# SmartSocket.net
KiCad netlist of a schematic drawn in Altium Designer
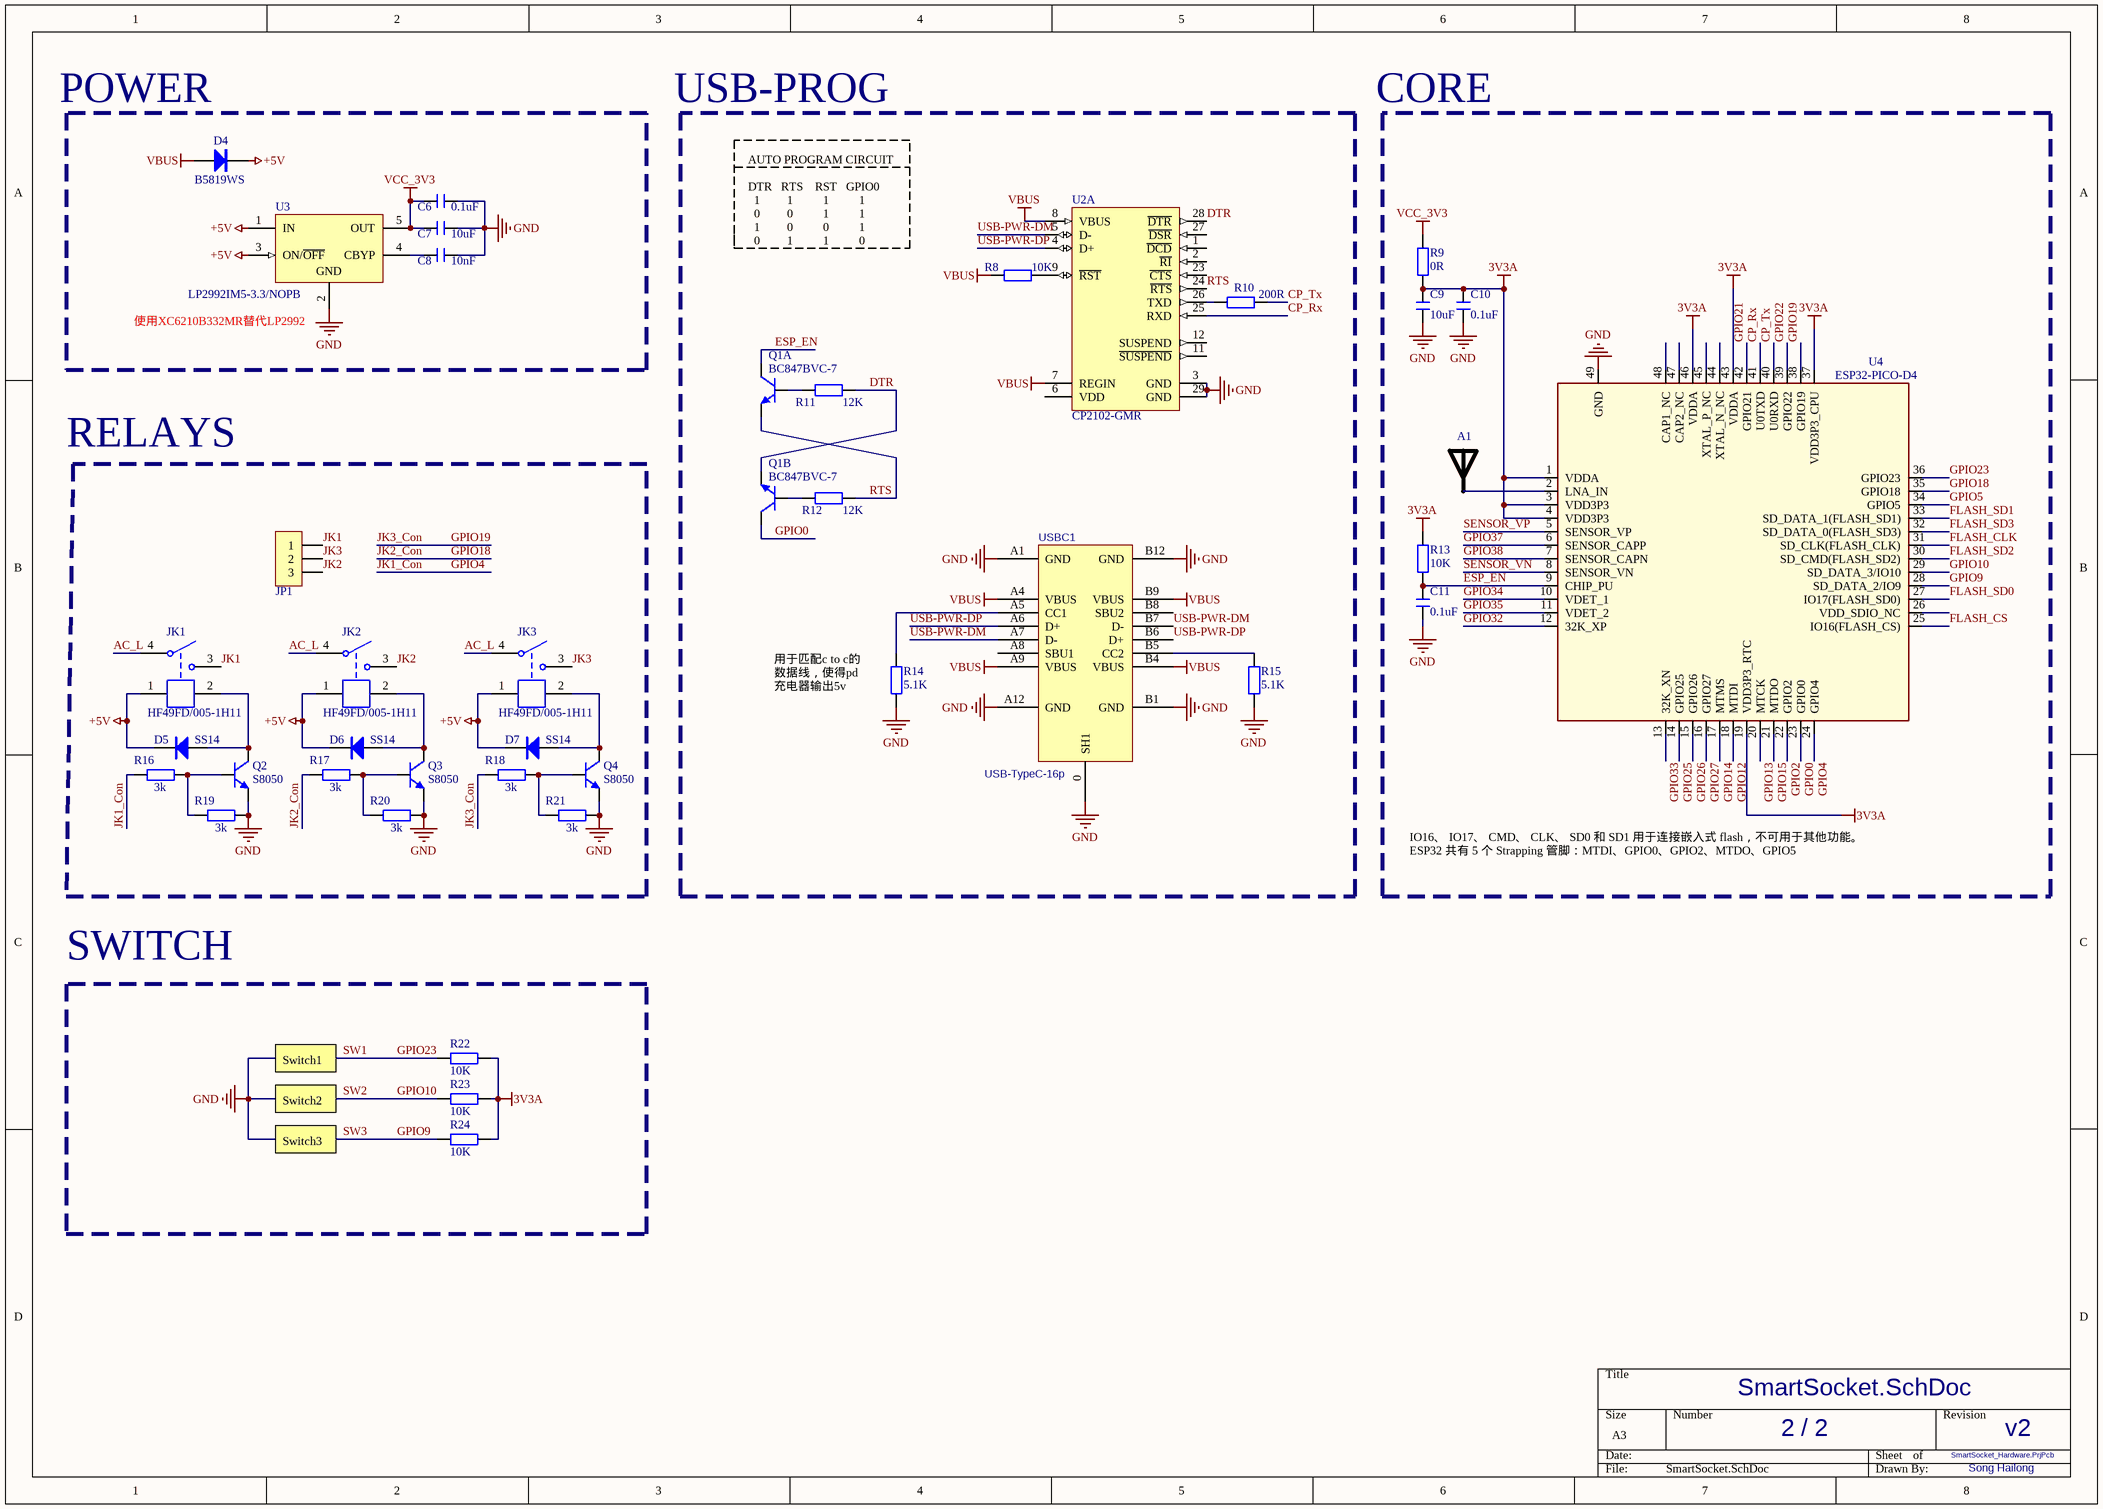
[diagram p0: SmartSocket.SchDoc]

(export (version "E")
  (design (tool "Eeschema 10.0.6"))
  (components
    (comp (ref "A1")
      (value "AN2051-245")
      (footprint "AN2051-245")
      (description "天线AN2051-245")
      (libsource (lib "海龍集成库") (part "ANT-Rainsun-AP2051"))
    )
    (comp (ref "C6")
      (value "0.1uF")
      (footprint "C 0402_L")
      (description "无极性贴片电容")
      (fields (field (name "版权归属") "源创客"))
      (libsource (lib "海龍集成库") (part "C"))
    )
    (comp (ref "C7")
      (value "10uF")
      (footprint "C 0402_L")
      (description "无极性贴片电容")
      (fields (field (name "版权归属") "源创客"))
      (libsource (lib "海龍集成库") (part "C"))
    )
    (comp (ref "C8")
      (value "10nF")
      (footprint "C 0402_L")
      (description "无极性贴片电容")
      (fields (field (name "版权归属") "源创客"))
      (libsource (lib "海龍集成库") (part "C"))
    )
    (comp (ref "C9")
      (value "10uF")
      (footprint "C 0402_L")
      (description "无极性贴片电容")
      (fields (field (name "版权归属") "源创客"))
      (libsource (lib "海龍集成库") (part "C"))
    )
    (comp (ref "C10")
      (value "0.1uF")
      (footprint "C 0402_L")
      (description "无极性贴片电容")
      (fields (field (name "版权归属") "源创客"))
      (libsource (lib "海龍集成库") (part "C"))
    )
    (comp (ref "C11")
      (value "0.1uF")
      (footprint "C 0402_L")
      (description "无极性贴片电容")
      (fields (field (name "版权归属") "源创客"))
      (libsource (lib "海龍集成库") (part "C"))
    )
    (comp (ref "D4")
      (value "B5819WS")
      (footprint "SOD-323")
      (description "肖特基二极管")
      (fields (field (name "版权归属") "源创客"))
      (libsource (lib "海龍集成库") (part "1N5819"))
    )
    (comp (ref "D5")
      (value "SS14")
      (footprint "SMA")
      (description "肖特基二极管")
      (fields (field (name "版权归属") "源创客"))
      (libsource (lib "海龍集成库") (part "SS14"))
    )
    (comp (ref "D6")
      (value "SS14")
      (footprint "SMA")
      (description "肖特基二极管")
      (fields (field (name "版权归属") "源创客"))
      (libsource (lib "海龍集成库") (part "SS14"))
    )
    (comp (ref "D7")
      (value "SS14")
      (footprint "SMA")
      (description "肖特基二极管")
      (fields (field (name "版权归属") "源创客"))
      (libsource (lib "海龍集成库") (part "SS14"))
    )
    (comp (ref "JK1")
      (value "HF49FD/005-1H11")
      (footprint "HF49-XX-1H11")
      (description "5V一组常开")
      (libsource (lib "海龍集成库") (part "HF49FD/005-1H11"))
    )
    (comp (ref "JK2")
      (value "HF49FD/005-1H11")
      (footprint "HF49-XX-1H11")
      (description "5V一组常开")
      (libsource (lib "海龍集成库") (part "HF49FD/005-1H11"))
    )
    (comp (ref "JK3")
      (value "HF49FD/005-1H11")
      (footprint "HF49-XX-1H11")
      (description "5V一组常开")
      (libsource (lib "海龍集成库") (part "HF49FD/005-1H11"))
    )
    (comp (ref "JP1")
      (value "HDR-1X3")
      (footprint "KF301-5.0-3P")
      (description "3P接插件")
      (fields (field (name "版权归属") "源创客"))
      (libsource (lib "海龍集成库") (part "Header 03 5.0"))
    )
    (comp (ref "Q1")
      (value "BC847BVC-7")
      (footprint "SOT563-6")
      (libsource (lib "海龍集成库") (part "BC847BVC-7"))
    )
    (comp (ref "Q2")
      (value "S8050")
      (footprint "SOT23-3N")
      (description "高频放大-NPN型")
      (fields (field (name "版权归属") "源创客"))
      (libsource (lib "海龍集成库") (part "8050-SMD"))
    )
    (comp (ref "Q3")
      (value "S8050")
      (footprint "SOT23-3N")
      (description "高频放大-NPN型")
      (fields (field (name "版权归属") "源创客"))
      (libsource (lib "海龍集成库") (part "8050-SMD"))
    )
    (comp (ref "Q4")
      (value "S8050")
      (footprint "SOT23-3N")
      (description "高频放大-NPN型")
      (fields (field (name "版权归属") "源创客"))
      (libsource (lib "海龍集成库") (part "8050-SMD"))
    )
    (comp (ref "R8")
      (value "10K")
      (footprint "R 0402_L")
      (description "贴片电阻")
      (fields (field (name "版权归属") "源创客"))
      (libsource (lib "海龍集成库") (part "R"))
    )
    (comp (ref "R9")
      (value "0R")
      (footprint "R 0402_L")
      (description "贴片电阻")
      (fields (field (name "版权归属") "源创客"))
      (libsource (lib "海龍集成库") (part "R"))
    )
    (comp (ref "R10")
      (value "200R")
      (footprint "R 0402_L")
      (description "贴片电阻")
      (fields (field (name "版权归属") "源创客"))
      (libsource (lib "海龍集成库") (part "R"))
    )
    (comp (ref "R11")
      (value "12K")
      (footprint "R 0402_L")
      (description "贴片电阻")
      (fields (field (name "版权归属") "源创客"))
      (libsource (lib "海龍集成库") (part "R"))
    )
    (comp (ref "R12")
      (value "12K")
      (footprint "R 0402_L")
      (description "贴片电阻")
      (fields (field (name "版权归属") "源创客"))
      (libsource (lib "海龍集成库") (part "R"))
    )
    (comp (ref "R13")
      (value "10K")
      (footprint "R 0402_L")
      (description "贴片电阻")
      (fields (field (name "版权归属") "源创客"))
      (libsource (lib "海龍集成库") (part "R"))
    )
    (comp (ref "R14")
      (value "5.1K")
      (footprint "R 0402_L")
      (description "贴片电阻")
      (fields (field (name "版权归属") "源创客"))
      (libsource (lib "海龍集成库") (part "R"))
    )
    (comp (ref "R15")
      (value "5.1K")
      (footprint "R 0402_L")
      (description "贴片电阻")
      (fields (field (name "版权归属") "源创客"))
      (libsource (lib "海龍集成库") (part "R"))
    )
    (comp (ref "R16")
      (value "3k")
      (footprint "R 0603_L")
      (description "贴片电阻")
      (fields (field (name "版权归属") "源创客"))
      (libsource (lib "海龍集成库") (part "R"))
    )
    (comp (ref "R17")
      (value "3k")
      (footprint "R 0603_L")
      (description "贴片电阻")
      (fields (field (name "版权归属") "源创客"))
      (libsource (lib "海龍集成库") (part "R"))
    )
    (comp (ref "R18")
      (value "3k")
      (footprint "R 0603_L")
      (description "贴片电阻")
      (fields (field (name "版权归属") "源创客"))
      (libsource (lib "海龍集成库") (part "R"))
    )
    (comp (ref "R19")
      (value "3k")
      (footprint "R 0603_L")
      (description "贴片电阻")
      (fields (field (name "版权归属") "源创客"))
      (libsource (lib "海龍集成库") (part "R"))
    )
    (comp (ref "R20")
      (value "3k")
      (footprint "R 0603_L")
      (description "贴片电阻")
      (fields (field (name "版权归属") "源创客"))
      (libsource (lib "海龍集成库") (part "R"))
    )
    (comp (ref "R21")
      (value "3k")
      (footprint "R 0603_L")
      (description "贴片电阻")
      (fields (field (name "版权归属") "源创客"))
      (libsource (lib "海龍集成库") (part "R"))
    )
    (comp (ref "R22")
      (value "10K")
      (footprint "R 0402_L")
      (description "贴片电阻")
      (fields (field (name "版权归属") "源创客"))
      (libsource (lib "U8Library") (part "R"))
    )
    (comp (ref "R23")
      (value "10K")
      (footprint "R 0402_L")
      (description "贴片电阻")
      (fields (field (name "版权归属") "源创客"))
      (libsource (lib "U8Library") (part "R"))
    )
    (comp (ref "R24")
      (value "10K")
      (footprint "R 0402_L")
      (description "贴片电阻")
      (fields (field (name "版权归属") "源创客"))
      (libsource (lib "U8Library") (part "R"))
    )
    (comp (ref "U2")
      (value "CP2102-GMR")
      (footprint "SLAB-QFN-28-3125x3125TP_M")
      (description "Single-Chip USB to URAT Bridge, 3.3 V, -40 to 85 degC, 28-Pin QFN, RoHS, Tape and Reel")
      (fields (field (name "MANUFACTURER") "Silicon Labs"))
      (libsource (lib "Altium Content Vault") (part "SLAB-CP210X-QFN-28-29"))
    )
    (comp (ref "U3")
      (value "LP2992IM5-3.3/NOPB")
      (footprint "DBV0005A_N")
      (description "Micropower 250 mA Low-Noise Ultra Low-Dropout Regulator, 5-pin SOT-23, Pb-Free")
      (fields (field (name "MANUFACTURER") "Texas Instruments"))
      (libsource (lib "Altium Content Vault") (part "PM-REG-LP2985-SOT5"))
    )
    (comp (ref "U4")
      (value "ESP32-PICO-D4")
      (footprint "QFN48")
      (libsource (lib "海龍集成库") (part "ESP32-PICO-D4"))
    )
    (comp (ref "USBC1")
      (value "USB-TypeC-16p")
      (footprint "TYPE-C-USB-16P-1")
      (libsource (lib "15.1 - type-c-sch") (part "USB-TypeC-16p"))
    )
  )
  (nets
    (net (code "1") (name "+5V") (class "Default")
      (node (ref "D4") (pin "2") (pinfunction "K_2") (pintype "passive"))
      (node (ref "D5") (pin "2") (pinfunction "K_2") (pintype "passive"))
      (node (ref "D6") (pin "2") (pinfunction "K_2") (pintype "passive"))
      (node (ref "D7") (pin "2") (pinfunction "K_2") (pintype "passive"))
      (node (ref "JK1") (pin "1") (pinfunction "1_1") (pintype "passive"))
      (node (ref "JK2") (pin "1") (pinfunction "1_1") (pintype "passive"))
      (node (ref "JK3") (pin "1") (pinfunction "1_1") (pintype "passive"))
      (node (ref "U3") (pin "1") (pinfunction "IN_1") (pintype "power_in"))
      (node (ref "U3") (pin "3") (pinfunction "ON/~{OFF}_3") (pintype "input"))
    )
    (net (code "2") (name "/AC_L") (class "Default")
      (node (ref "JK1") (pin "4") (pinfunction "4_4") (pintype "passive"))
      (node (ref "JK2") (pin "4") (pinfunction "4_4") (pintype "passive"))
      (node (ref "JK3") (pin "4") (pinfunction "4_4") (pintype "passive"))
    )
    (net (code "3") (name "/CP_Rx") (class "Default")
      (node (ref "U2") (pin "25") (pinfunction "RXD_25") (pintype "input"))
      (node (ref "U4") (pin "41") (pinfunction "U0TXD_41") (pintype "power_in"))
    )
    (net (code "4") (name "/CP_Tx") (class "Default")
      (node (ref "R10") (pin "2") (pinfunction "2_2") (pintype "passive"))
      (node (ref "U4") (pin "40") (pinfunction "U0RXD_40") (pintype "power_in"))
    )
    (net (code "5") (name "/DTR") (class "Default")
      (node (ref "Q1") (pin "4") (pinfunction "E2_4") (pintype "passive"))
      (node (ref "R11") (pin "2") (pinfunction "2_2") (pintype "passive"))
      (node (ref "U2") (pin "28") (pinfunction "~{DTR}_28") (pintype "output"))
    )
    (net (code "6") (name "/ESP_EN") (class "Default")
      (node (ref "C11") (pin "2") (pinfunction "2_2") (pintype "passive"))
      (node (ref "Q1") (pin "6") (pinfunction "C1_6") (pintype "passive"))
      (node (ref "R13") (pin "1") (pinfunction "1_1") (pintype "passive"))
      (node (ref "U4") (pin "9") (pinfunction "CHIP_PU_9") (pintype "passive"))
    )
    (net (code "7") (name "/FLASH_CLK") (class "Default")
      (node (ref "U4") (pin "31") (pinfunction "SD_CLK(FLASH_CLK)_31") (pintype "passive"))
    )
    (net (code "8") (name "/FLASH_CS") (class "Default")
      (node (ref "U4") (pin "25") (pinfunction "IO16(FLASH_CS)_25") (pintype "passive"))
    )
    (net (code "9") (name "/FLASH_SD0") (class "Default")
      (node (ref "U4") (pin "27") (pinfunction "IO17(FLASH_SD0)_27") (pintype "passive"))
    )
    (net (code "10") (name "/FLASH_SD1") (class "Default")
      (node (ref "U4") (pin "33") (pinfunction "SD_DATA_1(FLASH_SD1)_33") (pintype "passive"))
    )
    (net (code "11") (name "/FLASH_SD2") (class "Default")
      (node (ref "U4") (pin "30") (pinfunction "SD_CMD(FLASH_SD2)_30") (pintype "passive"))
    )
    (net (code "12") (name "/FLASH_SD3") (class "Default")
      (node (ref "U4") (pin "32") (pinfunction "SD_DATA_0(FLASH_SD3)_32") (pintype "passive"))
    )
    (net (code "13") (name "/GPIO0") (class "Default")
      (node (ref "Q1") (pin "3") (pinfunction "C2_3") (pintype "passive"))
      (node (ref "U4") (pin "23") (pinfunction "GPIO0_23") (pintype "passive"))
    )
    (net (code "14") (name "/GPIO2") (class "Default")
      (node (ref "U4") (pin "22") (pinfunction "GPIO2_22") (pintype "passive"))
    )
    (net (code "15") (name "/GPIO4") (class "Default")
      (node (ref "R16") (pin "2") (pinfunction "2_2") (pintype "passive"))
      (node (ref "U4") (pin "24") (pinfunction "GPIO4_24") (pintype "passive"))
    )
    (net (code "16") (name "/GPIO5") (class "Default")
      (node (ref "U4") (pin "34") (pinfunction "GPIO5_34") (pintype "passive"))
    )
    (net (code "17") (name "/GPIO9") (class "Default")
      (node (ref "R24") (pin "1") (pinfunction "1_1") (pintype "passive"))
      (node (ref "U4") (pin "28") (pinfunction "SD_DATA_2/IO9_28") (pintype "passive"))
    )
    (net (code "18") (name "/GPIO10") (class "Default")
      (node (ref "R23") (pin "1") (pinfunction "1_1") (pintype "passive"))
      (node (ref "U4") (pin "29") (pinfunction "SD_DATA_3/IO10_29") (pintype "passive"))
    )
    (net (code "19") (name "/GPIO12") (class "Default")
      (node (ref "U4") (pin "18") (pinfunction "MTDI_18") (pintype "passive"))
    )
    (net (code "20") (name "/GPIO13") (class "Default")
      (node (ref "U4") (pin "20") (pinfunction "MTCK_20") (pintype "passive"))
    )
    (net (code "21") (name "/GPIO14") (class "Default")
      (node (ref "U4") (pin "17") (pinfunction "MTMS_17") (pintype "passive"))
    )
    (net (code "22") (name "/GPIO15") (class "Default")
      (node (ref "U4") (pin "21") (pinfunction "MTDO_21") (pintype "passive"))
    )
    (net (code "23") (name "/GPIO18") (class "Default")
      (node (ref "R17") (pin "2") (pinfunction "2_2") (pintype "passive"))
      (node (ref "U4") (pin "35") (pinfunction "GPIO18_35") (pintype "passive"))
    )
    (net (code "24") (name "/GPIO19") (class "Default")
      (node (ref "R18") (pin "2") (pinfunction "2_2") (pintype "passive"))
      (node (ref "U4") (pin "38") (pinfunction "GPIO19_38") (pintype "passive"))
    )
    (net (code "25") (name "/GPIO21") (class "Default")
      (node (ref "U4") (pin "42") (pinfunction "GPIO21_42") (pintype "passive"))
    )
    (net (code "26") (name "/GPIO22") (class "Default")
      (node (ref "U4") (pin "39") (pinfunction "GPIO22_39") (pintype "passive"))
    )
    (net (code "27") (name "/GPIO23") (class "Default")
      (node (ref "R22") (pin "1") (pinfunction "1_1") (pintype "passive"))
      (node (ref "U4") (pin "36") (pinfunction "GPIO23_36") (pintype "passive"))
    )
    (net (code "28") (name "/GPIO25") (class "Default")
      (node (ref "U4") (pin "14") (pinfunction "GPIO25_14") (pintype "passive"))
    )
    (net (code "29") (name "/GPIO26") (class "Default")
      (node (ref "U4") (pin "15") (pinfunction "GPIO26_15") (pintype "passive"))
    )
    (net (code "30") (name "/GPIO27") (class "Default")
      (node (ref "U4") (pin "16") (pinfunction "GPIO27_16") (pintype "passive"))
    )
    (net (code "31") (name "/GPIO32") (class "Default")
      (node (ref "U4") (pin "12") (pinfunction "32K_XP_12") (pintype "passive"))
    )
    (net (code "32") (name "/GPIO33") (class "Default")
      (node (ref "U4") (pin "13") (pinfunction "32K_XN_13") (pintype "passive"))
    )
    (net (code "33") (name "/GPIO34") (class "Default")
      (node (ref "U4") (pin "10") (pinfunction "VDET_1_10") (pintype "passive"))
    )
    (net (code "34") (name "/GPIO35") (class "Default")
      (node (ref "U4") (pin "11") (pinfunction "VDET_2_11") (pintype "passive"))
    )
    (net (code "35") (name "/GPIO37") (class "Default")
      (node (ref "U4") (pin "6") (pinfunction "SENSOR_CAPP_6") (pintype "passive"))
    )
    (net (code "36") (name "/GPIO38") (class "Default")
      (node (ref "U4") (pin "7") (pinfunction "SENSOR_CAPN_7") (pintype "passive"))
    )
    (net (code "37") (name "/JK1") (class "Default")
      (node (ref "JK1") (pin "3") (pinfunction "3_3") (pintype "passive"))
      (node (ref "JP1") (pin "1") (pinfunction "1_1") (pintype "passive"))
    )
    (net (code "38") (name "/JK2") (class "Default")
      (node (ref "JK2") (pin "3") (pinfunction "3_3") (pintype "passive"))
      (node (ref "JP1") (pin "3") (pinfunction "3_3") (pintype "passive"))
    )
    (net (code "39") (name "/JK3") (class "Default")
      (node (ref "JK3") (pin "3") (pinfunction "3_3") (pintype "passive"))
      (node (ref "JP1") (pin "2") (pinfunction "2_2") (pintype "passive"))
    )
    (net (code "40") (name "/RTS") (class "Default")
      (node (ref "Q1") (pin "1") (pinfunction "E1_1") (pintype "passive"))
      (node (ref "R12") (pin "2") (pinfunction "2_2") (pintype "passive"))
      (node (ref "U2") (pin "24") (pinfunction "~{RTS}_24") (pintype "output"))
    )
    (net (code "41") (name "/SENSOR_VN") (class "Default")
      (node (ref "U4") (pin "8") (pinfunction "SENSOR_VN_8") (pintype "passive"))
    )
    (net (code "42") (name "/SENSOR_VP") (class "Default")
      (node (ref "U4") (pin "5") (pinfunction "SENSOR_VP_5") (pintype "passive"))
    )
    (net (code "43") (name "/USB-PWR-DM") (class "Default")
      (node (ref "U2") (pin "5") (pinfunction "D-_5") (pintype "bidirectional"))
      (node (ref "USBC1") (pin "A7") (pinfunction "D-_A7") (pintype "passive"))
      (node (ref "USBC1") (pin "B7") (pinfunction "D-_B7") (pintype "passive"))
    )
    (net (code "44") (name "/USB-PWR-DP") (class "Default")
      (node (ref "U2") (pin "4") (pinfunction "D+_4") (pintype "bidirectional"))
      (node (ref "USBC1") (pin "A6") (pinfunction "D+_A6") (pintype "passive"))
      (node (ref "USBC1") (pin "B6") (pinfunction "D+_B6") (pintype "passive"))
    )
    (net (code "45") (name "3V3A") (class "Default")
      (node (ref "C10") (pin "2") (pinfunction "2_2") (pintype "passive"))
      (node (ref "C9") (pin "2") (pinfunction "2_2") (pintype "passive"))
      (node (ref "R13") (pin "2") (pinfunction "2_2") (pintype "passive"))
      (node (ref "R22") (pin "2") (pinfunction "2_2") (pintype "passive"))
      (node (ref "R23") (pin "2") (pinfunction "2_2") (pintype "passive"))
      (node (ref "R24") (pin "2") (pinfunction "2_2") (pintype "passive"))
      (node (ref "R9") (pin "1") (pinfunction "1_1") (pintype "passive"))
      (node (ref "U4") (pin "1") (pinfunction "VDDA_1") (pintype "power_in"))
      (node (ref "U4") (pin "19") (pinfunction "VDD3P3_RTC_19") (pintype "power_in"))
      (node (ref "U4") (pin "3") (pinfunction "VDD3P3_3") (pintype "power_in"))
      (node (ref "U4") (pin "37") (pinfunction "VDD3P3_CPU_37") (pintype "power_in"))
      (node (ref "U4") (pin "4") (pinfunction "VDD3P3_4") (pintype "power_in"))
      (node (ref "U4") (pin "43") (pinfunction "VDDA_43") (pintype "power_in"))
      (node (ref "U4") (pin "46") (pinfunction "VDDA_46") (pintype "power_in"))
    )
    (net (code "46") (name "GND") (class "Default")
      (node (ref "C10") (pin "1") (pinfunction "1_1") (pintype "passive"))
      (node (ref "C11") (pin "1") (pinfunction "1_1") (pintype "passive"))
      (node (ref "C6") (pin "2") (pinfunction "2_2") (pintype "passive"))
      (node (ref "C7") (pin "2") (pinfunction "2_2") (pintype "passive"))
      (node (ref "C8") (pin "2") (pinfunction "2_2") (pintype "passive"))
      (node (ref "C9") (pin "1") (pinfunction "1_1") (pintype "passive"))
      (node (ref "Q2") (pin "2") (pinfunction "E_2") (pintype "passive"))
      (node (ref "Q3") (pin "2") (pinfunction "E_2") (pintype "passive"))
      (node (ref "Q4") (pin "2") (pinfunction "E_2") (pintype "passive"))
      (node (ref "R14") (pin "1") (pinfunction "1_1") (pintype "passive"))
      (node (ref "R15") (pin "1") (pinfunction "1_1") (pintype "passive"))
      (node (ref "R19") (pin "1") (pinfunction "1_1") (pintype "passive"))
      (node (ref "R20") (pin "1") (pinfunction "1_1") (pintype "passive"))
      (node (ref "R21") (pin "1") (pinfunction "1_1") (pintype "passive"))
      (node (ref "U2") (pin "29") (pinfunction "GND_29") (pintype "power_in"))
      (node (ref "U2") (pin "3") (pinfunction "GND_3") (pintype "power_in"))
      (node (ref "U3") (pin "2") (pinfunction "GND_2") (pintype "power_in"))
      (node (ref "U4") (pin "49") (pinfunction "GND_49") (pintype "power_in"))
      (node (ref "USBC1") (pin "0") (pinfunction "SH1_0") (pintype "passive"))
      (node (ref "USBC1") (pin "A1") (pinfunction "GND_A1") (pintype "passive"))
      (node (ref "USBC1") (pin "A12") (pinfunction "GND_A12") (pintype "passive"))
      (node (ref "USBC1") (pin "B1") (pinfunction "GND_B1") (pintype "passive"))
      (node (ref "USBC1") (pin "B12") (pinfunction "GND_B12") (pintype "passive"))
    )
    (net (code "47") (name "Net-(D5-A)") (class "Default")
      (node (ref "D5") (pin "1") (pinfunction "A_1") (pintype "passive"))
      (node (ref "JK1") (pin "2") (pinfunction "2_2") (pintype "passive"))
      (node (ref "Q2") (pin "3") (pinfunction "C_3") (pintype "passive"))
    )
    (net (code "48") (name "Net-(D6-A)") (class "Default")
      (node (ref "D6") (pin "1") (pinfunction "A_1") (pintype "passive"))
      (node (ref "JK2") (pin "2") (pinfunction "2_2") (pintype "passive"))
      (node (ref "Q3") (pin "3") (pinfunction "C_3") (pintype "passive"))
    )
    (net (code "49") (name "Net-(D7-A)") (class "Default")
      (node (ref "D7") (pin "1") (pinfunction "A_1") (pintype "passive"))
      (node (ref "JK3") (pin "2") (pinfunction "2_2") (pintype "passive"))
      (node (ref "Q4") (pin "3") (pinfunction "C_3") (pintype "passive"))
    )
    (net (code "50") (name "Net-(Q1A-B1)") (class "Default")
      (node (ref "Q1") (pin "2") (pinfunction "B1_2") (pintype "passive"))
      (node (ref "R11") (pin "1") (pinfunction "1_1") (pintype "passive"))
    )
    (net (code "51") (name "Net-(Q1B-B2)") (class "Default")
      (node (ref "Q1") (pin "5") (pinfunction "B2_5") (pintype "passive"))
      (node (ref "R12") (pin "1") (pinfunction "1_1") (pintype "passive"))
    )
    (net (code "52") (name "Net-(Q2-B)") (class "Default")
      (node (ref "Q2") (pin "1") (pinfunction "B_1") (pintype "passive"))
      (node (ref "R16") (pin "1") (pinfunction "1_1") (pintype "passive"))
      (node (ref "R19") (pin "2") (pinfunction "2_2") (pintype "passive"))
    )
    (net (code "53") (name "Net-(Q3-B)") (class "Default")
      (node (ref "Q3") (pin "1") (pinfunction "B_1") (pintype "passive"))
      (node (ref "R17") (pin "1") (pinfunction "1_1") (pintype "passive"))
      (node (ref "R20") (pin "2") (pinfunction "2_2") (pintype "passive"))
    )
    (net (code "54") (name "Net-(Q4-B)") (class "Default")
      (node (ref "Q4") (pin "1") (pinfunction "B_1") (pintype "passive"))
      (node (ref "R18") (pin "1") (pinfunction "1_1") (pintype "passive"))
      (node (ref "R21") (pin "2") (pinfunction "2_2") (pintype "passive"))
    )
    (net (code "55") (name "Net-(U2A-TXD)") (class "Default")
      (node (ref "R10") (pin "1") (pinfunction "1_1") (pintype "passive"))
      (node (ref "U2") (pin "26") (pinfunction "TXD_26") (pintype "output"))
    )
    (net (code "56") (name "Net-(U2A-~{RST})") (class "Default")
      (node (ref "R8") (pin "2") (pinfunction "2_2") (pintype "passive"))
      (node (ref "U2") (pin "9") (pinfunction "~{RST}_9") (pintype "bidirectional"))
    )
    (net (code "57") (name "Net-(U3-CBYP)") (class "Default")
      (node (ref "C8") (pin "1") (pinfunction "1_1") (pintype "passive"))
      (node (ref "U3") (pin "4") (pinfunction "CBYP_4") (pintype "passive"))
    )
    (net (code "58") (name "Net-(U4-LNA_IN)") (class "Default")
      (node (ref "A1") (pin "1") (pinfunction "1_1") (pintype "passive"))
      (node (ref "U4") (pin "2") (pinfunction "LNA_IN_2") (pintype "passive"))
    )
    (net (code "59") (name "Net-(USBC1-CC1)") (class "Default")
      (node (ref "R14") (pin "2") (pinfunction "2_2") (pintype "passive"))
      (node (ref "USBC1") (pin "A5") (pinfunction "CC1_A5") (pintype "passive"))
    )
    (net (code "60") (name "Net-(USBC1-CC2)") (class "Default")
      (node (ref "R15") (pin "2") (pinfunction "2_2") (pintype "passive"))
      (node (ref "USBC1") (pin "B5") (pinfunction "CC2_B5") (pintype "passive"))
    )
    (net (code "61") (name "VBUS") (class "Default")
      (node (ref "D4") (pin "1") (pinfunction "A_1") (pintype "passive"))
      (node (ref "R8") (pin "1") (pinfunction "1_1") (pintype "passive"))
      (node (ref "U2") (pin "7") (pinfunction "REGIN_7") (pintype "power_in"))
      (node (ref "U2") (pin "8") (pinfunction "VBUS_8") (pintype "input"))
      (node (ref "USBC1") (pin "A4") (pinfunction "VBUS_A4") (pintype "passive"))
      (node (ref "USBC1") (pin "A9") (pinfunction "VBUS_A9") (pintype "passive"))
      (node (ref "USBC1") (pin "B4") (pinfunction "VBUS_B4") (pintype "passive"))
      (node (ref "USBC1") (pin "B9") (pinfunction "VBUS_B9") (pintype "passive"))
    )
    (net (code "62") (name "VCC_3V3") (class "Default")
      (node (ref "C6") (pin "1") (pinfunction "1_1") (pintype "passive"))
      (node (ref "C7") (pin "1") (pinfunction "1_1") (pintype "passive"))
      (node (ref "R9") (pin "2") (pinfunction "2_2") (pintype "passive"))
      (node (ref "U3") (pin "5") (pinfunction "OUT_5") (pintype "power_in"))
    )
    (net (code "63") (name "unconnected-(U2A-SUSPEND-Pad12)") (class "Default")
      (node (ref "U2") (pin "12") (pinfunction "SUSPEND_12") (pintype "output"))
    )
    (net (code "64") (name "unconnected-(U2A-VDD-Pad6)") (class "Default")
      (node (ref "U2") (pin "6") (pinfunction "VDD_6") (pintype "power_in"))
    )
    (net (code "65") (name "unconnected-(U2A-~{CTS}-Pad23)") (class "Default")
      (node (ref "U2") (pin "23") (pinfunction "~{CTS}_23") (pintype "input"))
    )
    (net (code "66") (name "unconnected-(U2A-~{DCD}-Pad1)") (class "Default")
      (node (ref "U2") (pin "1") (pinfunction "~{DCD}_1") (pintype "input"))
    )
    (net (code "67") (name "unconnected-(U2A-~{DSR}-Pad27)") (class "Default")
      (node (ref "U2") (pin "27") (pinfunction "~{DSR}_27") (pintype "input"))
    )
    (net (code "68") (name "unconnected-(U2A-~{RI}-Pad2)") (class "Default")
      (node (ref "U2") (pin "2") (pinfunction "~{RI}_2") (pintype "input"))
    )
    (net (code "69") (name "unconnected-(U2A-~{SUSPEND}-Pad11)") (class "Default")
      (node (ref "U2") (pin "11") (pinfunction "~{SUSPEND}_11") (pintype "output"))
    )
    (net (code "70") (name "unconnected-(U4-CAP1_NC-Pad48)") (class "Default")
      (node (ref "U4") (pin "48") (pinfunction "CAP1_NC_48") (pintype "passive"))
    )
    (net (code "71") (name "unconnected-(U4-CAP2_NC-Pad47)") (class "Default")
      (node (ref "U4") (pin "47") (pinfunction "CAP2_NC_47") (pintype "passive"))
    )
    (net (code "72") (name "unconnected-(U4-VDD_SDIO_NC-Pad26)") (class "Default")
      (node (ref "U4") (pin "26") (pinfunction "VDD_SDIO_NC_26") (pintype "passive"))
    )
    (net (code "73") (name "unconnected-(U4-XTAL_N_NC-Pad44)") (class "Default")
      (node (ref "U4") (pin "44") (pinfunction "XTAL_N_NC_44") (pintype "passive"))
    )
    (net (code "74") (name "unconnected-(U4-XTAL_P_NC-Pad45)") (class "Default")
      (node (ref "U4") (pin "45") (pinfunction "XTAL_P_NC_45") (pintype "passive"))
    )
    (net (code "75") (name "unconnected-(USBC1-SBU1-PadA8)") (class "Default")
      (node (ref "USBC1") (pin "A8") (pinfunction "SBU1_A8") (pintype "passive"))
    )
    (net (code "76") (name "unconnected-(USBC1-SBU2-PadB8)") (class "Default")
      (node (ref "USBC1") (pin "B8") (pinfunction "SBU2_B8") (pintype "passive"))
    )
  )
)
